# v3_0.net
KiCad netlist of a schematic drawn in Altium Designer
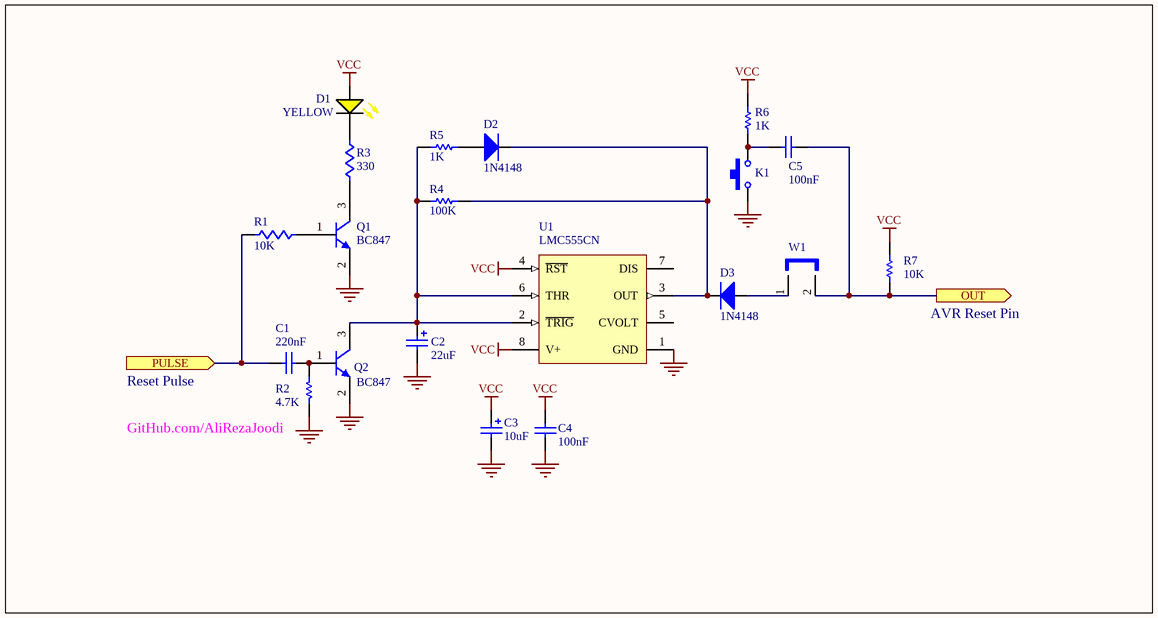
[diagram p0: v3.0.SchDoc]

(export (version "E")
  (design (tool "Eeschema 10.0.6"))
  (components
    (comp (ref "C1")
      (value "220nF")
      (footprint "RESC3216N")
      (description "Capacitor")
      (fields (field (name "Comment") "Cap") (field (name "PUBLISHER") "Altium Limited"))
      (libsource (lib "Miscellaneous Devices") (part "Cap"))
    )
    (comp (ref "C2")
      (value "22uF")
      (footprint "Cap_B")
      (description "Polarized Capacitor (Radial)")
      (fields
        (field (name "MANUFACTURER") "Generic Components")
        (field (name "Comment") "Capacitor")
        (field (name "PUBLISHER") "Altium Limited")
      )
      (libsource (lib "Miscellaneous Devices") (part "Cap Pol1"))
    )
    (comp (ref "C3")
      (value "10uF")
      (footprint "Cap_B")
      (description "Polarized Capacitor (Radial)")
      (fields
        (field (name "MANUFACTURER") "Generic Components")
        (field (name "Comment") "Capacitor")
        (field (name "PUBLISHER") "Altium Limited")
      )
      (libsource (lib "Miscellaneous Devices") (part "Cap Pol1"))
    )
    (comp (ref "C4")
      (value "100nF")
      (footprint "0805")
      (description "Capacitor")
      (fields
        (field (name "MANUFACTURER") "Generic Components")
        (field (name "Comment") "Cap")
        (field (name "PUBLISHER") "Altium Limited")
      )
      (libsource (lib "Miscellaneous Devices") (part "Cap"))
    )
    (comp (ref "C5")
      (value "100nF")
      (footprint "0805")
      (description "Capacitor")
      (fields
        (field (name "MANUFACTURER") "Generic Components")
        (field (name "Comment") "Cap")
        (field (name "PUBLISHER") "Altium Limited")
      )
      (libsource (lib "Miscellaneous Devices") (part "Cap"))
    )
    (comp (ref "D1")
      (value "YELLOW")
      (footprint "LED_THD_3MM_YELLOW_R")
      (description "LED, Yellow")
      (fields (field (name "MANUFACTURER") "Generic Components") (field (name "PUBLISHER") "Altium Limited"))
      (libsource (lib "Display") (part "LED_YELLOW"))
    )
    (comp (ref "D2")
      (value "1N4148")
      (footprint "0805_Diode")
      (description "Default Diode")
      (fields
        (field (name "MANUFACTURER") "Generic Components")
        (field (name "Comment") "Diode")
        (field (name "PUBLISHER") "Altium Limited")
      )
      (libsource (lib "Miscellaneous Devices") (part "Diode"))
    )
    (comp (ref "D3")
      (value "1N4148")
      (footprint "0805_Diode")
      (description "Default Diode")
      (fields
        (field (name "MANUFACTURER") "Generic Components")
        (field (name "Comment") "Diode")
        (field (name "PUBLISHER") "Altium Limited")
      )
      (libsource (lib "Miscellaneous Devices") (part "Diode"))
    )
    (comp (ref "K1")
      (value "Switch_SW-PB")
      (footprint "SWPBT_SPST_6X6X4")
      (description "Switch, SW-PB")
      (fields (field (name "MANUFACTURER") "Generic Components") (field (name "PUBLISHER") "Altium Limited"))
      (libsource (lib "Passive") (part "Switch_SW-PB_2Form"))
    )
    (comp (ref "Q1")
      (value "BC847")
      (footprint "SOT23-3N")
      (description "Silicon Bipolar Transistor")
      (fields (field (name "Comment") "NPN"))
      (libsource (lib "my Libraries") (part "BC847"))
    )
    (comp (ref "Q2")
      (value "BC847")
      (footprint "SOT23-3N")
      (description "Silicon Bipolar Transistor")
      (fields (field (name "Comment") "NPN"))
      (libsource (lib "my Libraries") (part "BC847"))
    )
    (comp (ref "R1")
      (value "10K")
      (footprint "0805")
      (description "Resistor")
      (fields
        (field (name "MANUFACTURER") "Generic Components")
        (field (name "Comment") "RES")
        (field (name "PUBLISHER") "Altium Limited")
      )
      (libsource (lib "") (part "Res1_1"))
    )
    (comp (ref "R2")
      (value "4.7K")
      (footprint "0805")
      (description "Resistor")
      (fields (field (name "Comment") "Res1") (field (name "PUBLISHER") "Altium Limited"))
      (libsource (lib "Miscellaneous Devices") (part "Res1"))
    )
    (comp (ref "R3")
      (value "330")
      (footprint "0805")
      (description "Resistor")
      (fields
        (field (name "MANUFACTURER") "Generic Components")
        (field (name "Comment") "RES")
        (field (name "PUBLISHER") "Altium Limited")
      )
      (libsource (lib "") (part "Res1_1"))
    )
    (comp (ref "R4")
      (value "100K")
      (footprint "0805")
      (description "Resistor")
      (fields (field (name "Comment") "Res1") (field (name "PUBLISHER") "Altium Limited"))
      (libsource (lib "Miscellaneous Devices") (part "Res1"))
    )
    (comp (ref "R5")
      (value "1K")
      (footprint "0805")
      (description "Resistor")
      (fields (field (name "Comment") "Res1") (field (name "PUBLISHER") "Altium Limited"))
      (libsource (lib "Miscellaneous Devices") (part "Res1"))
    )
    (comp (ref "R6")
      (value "1K")
      (footprint "0805")
      (description "Resistor")
      (fields (field (name "MANUFACTURER") "Generic Components") (field (name "PUBLISHER") "Altium Limited"))
      (libsource (lib "Miscellaneous Devices") (part "Res1"))
    )
    (comp (ref "R7")
      (value "10K")
      (footprint "0805")
      (description "Resistor")
      (fields
        (field (name "MANUFACTURER") "Generic Components")
        (field (name "Comment") "Res1")
        (field (name "PUBLISHER") "Altium Limited")
      )
      (libsource (lib "Miscellaneous Devices") (part "Res1"))
    )
    (comp (ref "U1")
      (value "LMC555CN")
      (footprint "SOP127P636-8N")
      (description "CMOS Timer, 8-pin MDIP")
      (fields
        (field (name "MANUFACTURER") "National Semiconductor")
        (field (name "PUBLISHER") "Altium Limited")
      )
      (libsource (lib "NSC Analog") (part "LMC555CN"))
    )
    (comp (ref "W1")
      (value "Jumper 2pin")
      (footprint "HDR1X2")
      (description "Jumper Wire")
      (fields (field (name "MANUFACTURER") "Generic Components") (field (name "PUBLISHER") "Altium Limited"))
      (libsource (lib "my Libraries") (part "Jumper 2pin"))
    )
  )
  (nets
    (net (code "1") (name "/OUT") (class "Default")
      (node (ref "C5") (pin "1") (pinfunction "1_1") (pintype "passive"))
      (node (ref "R7") (pin "2") (pinfunction "2_2") (pintype "passive"))
      (node (ref "W1") (pin "2") (pinfunction "2_2") (pintype "passive"))
    )
    (net (code "2") (name "/PULSE") (class "Default")
      (node (ref "C1") (pin "1") (pinfunction "1_1") (pintype "passive"))
      (node (ref "R1") (pin "1") (pinfunction "1_1") (pintype "passive"))
    )
    (net (code "3") (name "GND") (class "Default")
      (node (ref "C2") (pin "2") (pinfunction "2_2") (pintype "passive"))
      (node (ref "C3") (pin "2") (pinfunction "2_2") (pintype "passive"))
      (node (ref "C4") (pin "1") (pinfunction "1_1") (pintype "passive"))
      (node (ref "K1") (pin "1") (pinfunction "1_1") (pintype "passive"))
      (node (ref "Q1") (pin "2") (pinfunction "E_2") (pintype "passive"))
      (node (ref "Q2") (pin "2") (pinfunction "E_2") (pintype "passive"))
      (node (ref "R2") (pin "2") (pinfunction "2_2") (pintype "passive"))
      (node (ref "U1") (pin "1") (pinfunction "GND_1") (pintype "power_in"))
    )
    (net (code "4") (name "Net-(C5-Pad2)") (class "Default")
      (node (ref "C5") (pin "2") (pinfunction "2_2") (pintype "passive"))
      (node (ref "K1") (pin "2") (pinfunction "2_2") (pintype "passive"))
      (node (ref "R6") (pin "2") (pinfunction "2_2") (pintype "passive"))
    )
    (net (code "5") (name "Net-(D1-K)") (class "Default")
      (node (ref "D1") (pin "2") (pinfunction "K_2") (pintype "passive"))
      (node (ref "R3") (pin "1") (pinfunction "1_1") (pintype "passive"))
    )
    (net (code "6") (name "Net-(D2-A)") (class "Default")
      (node (ref "D2") (pin "1") (pinfunction "A_1") (pintype "passive"))
      (node (ref "R5") (pin "2") (pinfunction "2_2") (pintype "passive"))
    )
    (net (code "7") (name "Net-(D2-K)") (class "Default")
      (node (ref "D2") (pin "2") (pinfunction "K_2") (pintype "passive"))
      (node (ref "D3") (pin "2") (pinfunction "K_2") (pintype "passive"))
      (node (ref "R4") (pin "2") (pinfunction "2_2") (pintype "passive"))
      (node (ref "U1") (pin "3") (pinfunction "OUT_3") (pintype "output"))
    )
    (net (code "8") (name "Net-(D3-A)") (class "Default")
      (node (ref "D3") (pin "1") (pinfunction "A_1") (pintype "passive"))
      (node (ref "W1") (pin "1") (pinfunction "1_1") (pintype "passive"))
    )
    (net (code "9") (name "Net-(Q1-B)") (class "Default")
      (node (ref "Q1") (pin "1") (pinfunction "B_1") (pintype "passive"))
      (node (ref "R1") (pin "2") (pinfunction "2_2") (pintype "passive"))
    )
    (net (code "10") (name "Net-(Q1-C)") (class "Default")
      (node (ref "Q1") (pin "3") (pinfunction "C_3") (pintype "passive"))
      (node (ref "R3") (pin "2") (pinfunction "2_2") (pintype "passive"))
    )
    (net (code "11") (name "Net-(Q2-B)") (class "Default")
      (node (ref "C1") (pin "2") (pinfunction "2_2") (pintype "passive"))
      (node (ref "Q2") (pin "1") (pinfunction "B_1") (pintype "passive"))
      (node (ref "R2") (pin "1") (pinfunction "1_1") (pintype "passive"))
    )
    (net (code "12") (name "Net-(Q2-C)") (class "Default")
      (node (ref "C2") (pin "1") (pinfunction "1_1") (pintype "passive"))
      (node (ref "Q2") (pin "3") (pinfunction "C_3") (pintype "passive"))
      (node (ref "R4") (pin "1") (pinfunction "1_1") (pintype "passive"))
      (node (ref "R5") (pin "1") (pinfunction "1_1") (pintype "passive"))
      (node (ref "U1") (pin "2") (pinfunction "~{TRIG}_2") (pintype "input"))
      (node (ref "U1") (pin "6") (pinfunction "THR_6") (pintype "input"))
    )
    (net (code "13") (name "VCC") (class "Default")
      (node (ref "C3") (pin "1") (pinfunction "1_1") (pintype "passive"))
      (node (ref "C4") (pin "2") (pinfunction "2_2") (pintype "passive"))
      (node (ref "D1") (pin "1") (pinfunction "A_1") (pintype "passive"))
      (node (ref "R6") (pin "1") (pinfunction "1_1") (pintype "passive"))
      (node (ref "R7") (pin "1") (pinfunction "1_1") (pintype "passive"))
      (node (ref "U1") (pin "4") (pinfunction "~{RST}_4") (pintype "input"))
      (node (ref "U1") (pin "8") (pinfunction "V+_8") (pintype "power_in"))
    )
    (net (code "14") (name "unconnected-(U1-CVOLT-Pad5)") (class "Default")
      (node (ref "U1") (pin "5") (pinfunction "CVOLT_5") (pintype "passive"))
    )
    (net (code "15") (name "unconnected-(U1-DIS-Pad7)") (class "Default")
      (node (ref "U1") (pin "7") (pinfunction "DIS_7") (pintype "open_collector"))
    )
  )
)
